# H00R20.net
KiCad netlist of a schematic drawn in EAGLE
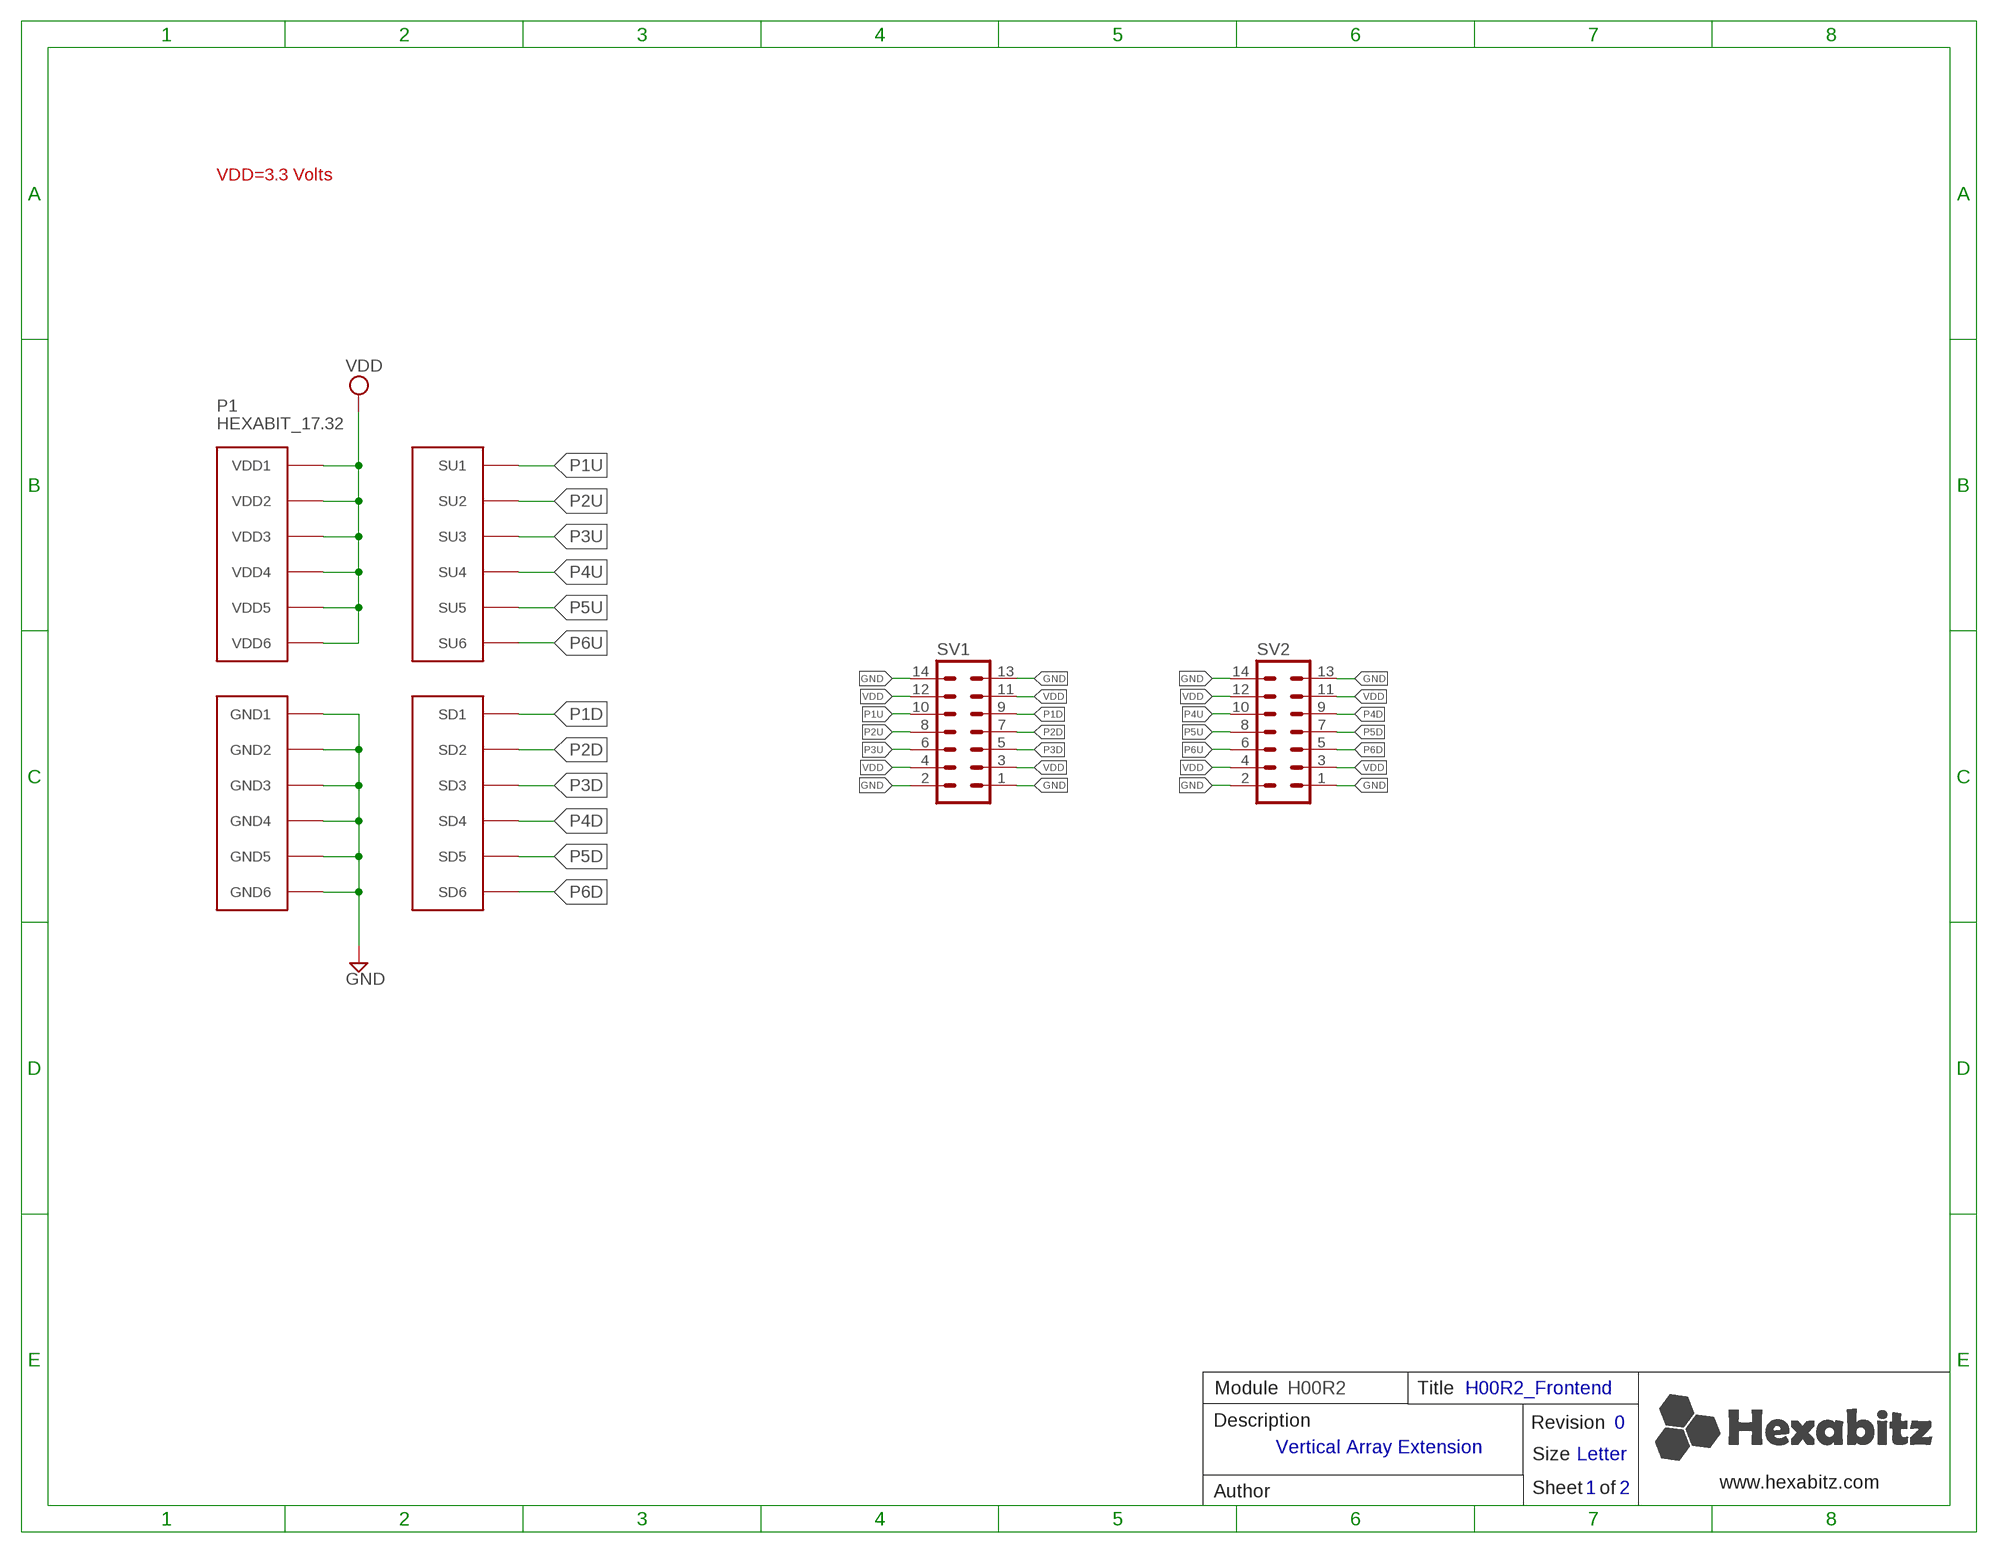
[diagram p0: schematic, sheet 1]

(export (version "E")
  (design (tool "Eeschema 10.0.6"))
  (components
    (comp (ref "P1")
      (value "HEXABIT_17.32")
      (footprint "eagle-import:HEXABIT_17.32")
      (libsource (lib "eagle-import") (part "HEXABIT_?17.32"))
    )
    (comp (ref "SV1")
      (value "MA07-2")
      (footprint "eagle-import:MA07-2")
      (libsource (lib "eagle-import") (part "MA07-2"))
    )
    (comp (ref "SV2")
      (value "MA07-2")
      (footprint "eagle-import:MA07-2")
      (libsource (lib "eagle-import") (part "MA07-2"))
    )
  )
  (nets
    (net (code "1") (name "GND") (class "Default")
      (node (ref "P1") (pin "PAD_PD10") (pinfunction "GND4_PAD_PD10") (pintype "power_in"))
      (node (ref "P1") (pin "PAD_PD11") (pinfunction "GND5_PAD_PD11") (pintype "power_in"))
      (node (ref "P1") (pin "PAD_PD12") (pinfunction "GND6_PAD_PD12") (pintype "power_in"))
      (node (ref "P1") (pin "PAD_PD7") (pinfunction "GND1_PAD_PD7") (pintype "power_in"))
      (node (ref "P1") (pin "PAD_PD8") (pinfunction "GND2_PAD_PD8") (pintype "power_in"))
      (node (ref "P1") (pin "PAD_PD9") (pinfunction "GND3_PAD_PD9") (pintype "power_in"))
      (node (ref "SV1") (pin "1") (pinfunction "1_1") (pintype "passive"))
      (node (ref "SV1") (pin "13") (pinfunction "13_13") (pintype "passive"))
      (node (ref "SV1") (pin "14") (pinfunction "14_14") (pintype "passive"))
      (node (ref "SV1") (pin "2") (pinfunction "2_2") (pintype "passive"))
      (node (ref "SV2") (pin "1") (pinfunction "1_1") (pintype "passive"))
      (node (ref "SV2") (pin "13") (pinfunction "13_13") (pintype "passive"))
      (node (ref "SV2") (pin "14") (pinfunction "14_14") (pintype "passive"))
      (node (ref "SV2") (pin "2") (pinfunction "2_2") (pintype "passive"))
    )
    (net (code "2") (name "P1D") (class "Default")
      (node (ref "P1") (pin "PAD_PD1") (pinfunction "SD1_PAD_PD1") (pintype "bidirectional"))
      (node (ref "SV1") (pin "9") (pinfunction "9_9") (pintype "passive"))
    )
    (net (code "3") (name "P1U") (class "Default")
      (node (ref "P1") (pin "PAD_PU1") (pinfunction "SU1_PAD_PU1") (pintype "bidirectional"))
      (node (ref "SV1") (pin "10") (pinfunction "10_10") (pintype "passive"))
    )
    (net (code "4") (name "P2D") (class "Default")
      (node (ref "P1") (pin "PAD_PD2") (pinfunction "SD2_PAD_PD2") (pintype "bidirectional"))
      (node (ref "SV1") (pin "7") (pinfunction "7_7") (pintype "passive"))
    )
    (net (code "5") (name "P2U") (class "Default")
      (node (ref "P1") (pin "PAD_PU2") (pinfunction "SU2_PAD_PU2") (pintype "bidirectional"))
      (node (ref "SV1") (pin "8") (pinfunction "8_8") (pintype "passive"))
    )
    (net (code "6") (name "P3D") (class "Default")
      (node (ref "P1") (pin "PAD_PD3") (pinfunction "SD3_PAD_PD3") (pintype "bidirectional"))
      (node (ref "SV1") (pin "5") (pinfunction "5_5") (pintype "passive"))
    )
    (net (code "7") (name "P3U") (class "Default")
      (node (ref "P1") (pin "PAD_PU3") (pinfunction "SU3_PAD_PU3") (pintype "bidirectional"))
      (node (ref "SV1") (pin "6") (pinfunction "6_6") (pintype "passive"))
    )
    (net (code "8") (name "P4D") (class "Default")
      (node (ref "P1") (pin "PAD_PD4") (pinfunction "SD4_PAD_PD4") (pintype "bidirectional"))
      (node (ref "SV2") (pin "9") (pinfunction "9_9") (pintype "passive"))
    )
    (net (code "9") (name "P4U") (class "Default")
      (node (ref "P1") (pin "PAD_PU4") (pinfunction "SU4_PAD_PU4") (pintype "bidirectional"))
      (node (ref "SV2") (pin "10") (pinfunction "10_10") (pintype "passive"))
    )
    (net (code "10") (name "P5D") (class "Default")
      (node (ref "P1") (pin "PAD_PD5") (pinfunction "SD5_PAD_PD5") (pintype "bidirectional"))
      (node (ref "SV2") (pin "7") (pinfunction "7_7") (pintype "passive"))
    )
    (net (code "11") (name "P5U") (class "Default")
      (node (ref "P1") (pin "PAD_PU5") (pinfunction "SU5_PAD_PU5") (pintype "bidirectional"))
      (node (ref "SV2") (pin "8") (pinfunction "8_8") (pintype "passive"))
    )
    (net (code "12") (name "P6D") (class "Default")
      (node (ref "P1") (pin "PAD_PD6") (pinfunction "SD6_PAD_PD6") (pintype "bidirectional"))
      (node (ref "SV2") (pin "5") (pinfunction "5_5") (pintype "passive"))
    )
    (net (code "13") (name "P6U") (class "Default")
      (node (ref "P1") (pin "PAD_PU6") (pinfunction "SU6_PAD_PU6") (pintype "bidirectional"))
      (node (ref "SV2") (pin "6") (pinfunction "6_6") (pintype "passive"))
    )
    (net (code "14") (name "VDD") (class "Default")
      (node (ref "P1") (pin "PAD_PU10") (pinfunction "VDD4_PAD_PU10") (pintype "power_in"))
      (node (ref "P1") (pin "PAD_PU11") (pinfunction "VDD5_PAD_PU11") (pintype "power_in"))
      (node (ref "P1") (pin "PAD_PU12") (pinfunction "VDD6_PAD_PU12") (pintype "power_in"))
      (node (ref "P1") (pin "PAD_PU7") (pinfunction "VDD1_PAD_PU7") (pintype "power_in"))
      (node (ref "P1") (pin "PAD_PU8") (pinfunction "VDD2_PAD_PU8") (pintype "power_in"))
      (node (ref "P1") (pin "PAD_PU9") (pinfunction "VDD3_PAD_PU9") (pintype "power_in"))
      (node (ref "SV1") (pin "11") (pinfunction "11_11") (pintype "passive"))
      (node (ref "SV1") (pin "12") (pinfunction "12_12") (pintype "passive"))
      (node (ref "SV1") (pin "3") (pinfunction "3_3") (pintype "passive"))
      (node (ref "SV1") (pin "4") (pinfunction "4_4") (pintype "passive"))
      (node (ref "SV2") (pin "11") (pinfunction "11_11") (pintype "passive"))
      (node (ref "SV2") (pin "12") (pinfunction "12_12") (pintype "passive"))
      (node (ref "SV2") (pin "3") (pinfunction "3_3") (pintype "passive"))
      (node (ref "SV2") (pin "4") (pinfunction "4_4") (pintype "passive"))
    )
  )
)
